# Ethernet.net
KiCad netlist of a schematic drawn in Altium Designer
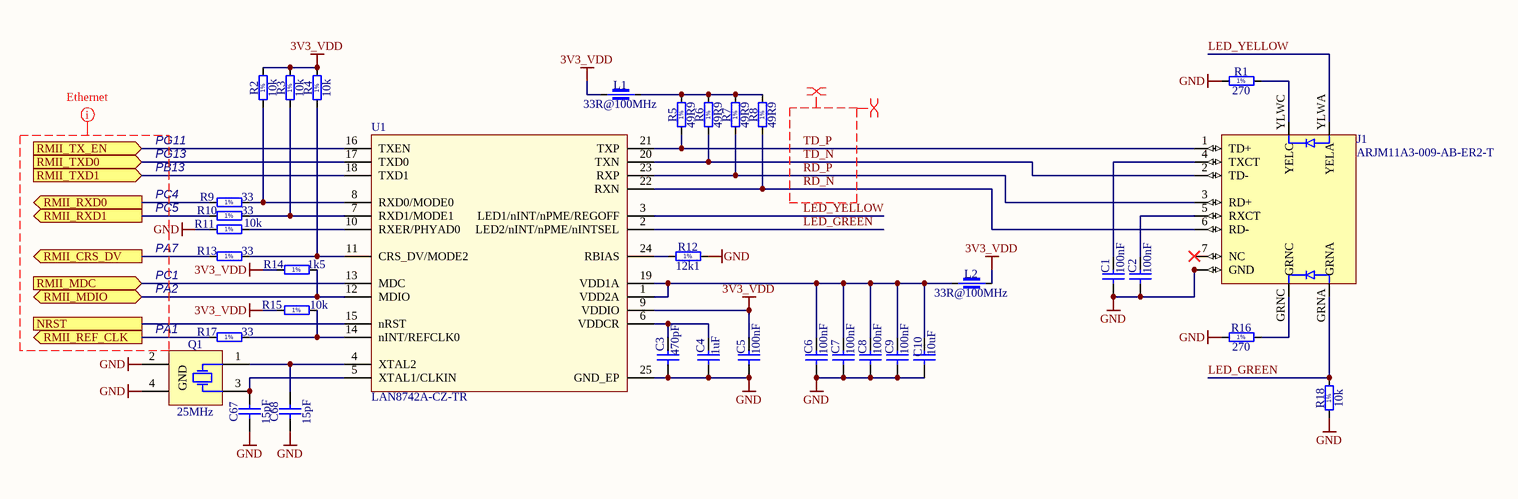
[diagram p0: Ethernet.SchDoc]

(export (version "E")
  (design (tool "Eeschema 10.0.6"))
  (components
    (comp (ref "C1")
      (value "100nF")
      (footprint "CAPC1005X55N")
      (description "Non-polarised capacitor")
      (fields
        (field (name "PART NUMBER") "CC0402_100NF_16V_10%_X7R")
        (field (name "VOLTAGE") "16V")
        (field (name "AUTHOR") "CERN DEM JLC")
      )
      (libsource (lib "Capacitors") (part "Capacitor - non polarized"))
    )
    (comp (ref "C2")
      (value "100nF")
      (footprint "CAPC1005X55N")
      (description "Non-polarised capacitor")
      (fields
        (field (name "PART NUMBER") "CC0402_100NF_16V_10%_X7R")
        (field (name "VOLTAGE") "16V")
        (field (name "AUTHOR") "CERN DEM JLC")
      )
      (libsource (lib "Capacitors") (part "Capacitor - non polarized"))
    )
    (comp (ref "C3")
      (value "470pF")
      (footprint "CAPC1005X55N")
      (description "Non-polarised capacitor")
      (fields
        (field (name "PART NUMBER") "CC0402_470PF_50V_10%_X7R")
        (field (name "VOLTAGE") "50V")
        (field (name "AUTHOR") "CERN DEM JLC")
      )
      (libsource (lib "Capacitors") (part "Capacitor - non polarized"))
    )
    (comp (ref "C4")
      (value "1uF")
      (footprint "CAPC1005X55N")
      (description "Non-polarised capacitor")
      (fields
        (field (name "PART NUMBER") "CC0402_1UF_16V_10%_X5R")
        (field (name "VOLTAGE") "16V")
        (field (name "AUTHOR") "CERN DEM JLC")
      )
      (libsource (lib "Capacitors") (part "Capacitor - non polarized"))
    )
    (comp (ref "C5")
      (value "100nF")
      (footprint "CAPC1005X55N")
      (description "Non-polarised capacitor")
      (fields
        (field (name "PART NUMBER") "CC0402_100NF_16V_10%_X7R")
        (field (name "VOLTAGE") "16V")
        (field (name "AUTHOR") "CERN DEM JLC")
      )
      (libsource (lib "Capacitors") (part "Capacitor - non polarized"))
    )
    (comp (ref "C6")
      (value "100nF")
      (footprint "CAPC1005X55N")
      (description "Non-polarised capacitor")
      (fields
        (field (name "PART NUMBER") "CC0402_100NF_16V_10%_X7R")
        (field (name "VOLTAGE") "16V")
        (field (name "AUTHOR") "CERN DEM JLC")
      )
      (libsource (lib "Capacitors") (part "Capacitor - non polarized"))
    )
    (comp (ref "C7")
      (value "100nF")
      (footprint "CAPC1005X55N")
      (description "Non-polarised capacitor")
      (fields
        (field (name "PART NUMBER") "CC0402_100NF_16V_10%_X7R")
        (field (name "VOLTAGE") "16V")
        (field (name "AUTHOR") "CERN DEM JLC")
      )
      (libsource (lib "Capacitors") (part "Capacitor - non polarized"))
    )
    (comp (ref "C8")
      (value "100nF")
      (footprint "CAPC1005X55N")
      (description "Non-polarised capacitor")
      (fields
        (field (name "PART NUMBER") "CC0402_100NF_16V_10%_X7R")
        (field (name "VOLTAGE") "16V")
        (field (name "AUTHOR") "CERN DEM JLC")
      )
      (libsource (lib "Capacitors") (part "Capacitor - non polarized"))
    )
    (comp (ref "C9")
      (value "100nF")
      (footprint "CAPC1005X55N")
      (description "Non-polarised capacitor")
      (fields
        (field (name "PART NUMBER") "CC0402_100NF_16V_10%_X7R")
        (field (name "VOLTAGE") "16V")
        (field (name "AUTHOR") "CERN DEM JLC")
      )
      (libsource (lib "Capacitors") (part "Capacitor - non polarized"))
    )
    (comp (ref "C10")
      (value "10uF")
      (footprint "CAPC1005X70N")
      (description "Non-polarised capacitor")
      (fields
        (field (name "PART NUMBER") "CC0402_10UF_6.3V_20%_X5R")
        (field (name "VOLTAGE") "6.3V")
        (field (name "AUTHOR") "CERN DEM JLC")
      )
      (libsource (lib "Capacitors") (part "Capacitor - non polarized"))
    )
    (comp (ref "C67")
      (value "15pF")
      (footprint "CAPC1005X55N")
      (description "Non-polarised capacitor")
      (fields
        (field (name "PART NUMBER") "CC0402_15PF_50V_5%_C0G")
        (field (name "VOLTAGE") "50V")
        (field (name "AUTHOR") "CERN DEM JLC")
      )
      (libsource (lib "Capacitors") (part "Capacitor - non polarized"))
    )
    (comp (ref "C68")
      (value "15pF")
      (footprint "CAPC1005X55N")
      (description "Non-polarised capacitor")
      (fields
        (field (name "PART NUMBER") "CC0402_15PF_50V_5%_C0G")
        (field (name "VOLTAGE") "50V")
        (field (name "AUTHOR") "CERN DEM JLC")
      )
      (libsource (lib "Capacitors") (part "Capacitor - non polarized"))
    )
    (comp (ref "J1")
      (value "ARJM11A3-009-AB-ER2-T")
      (footprint "ARJM11A3-009-AB-ER2-T")
      (description "1 Port RJ45 Magjack Connector Through Hole 10/100 Base-T, AutoMDIX")
      (fields (field (name "MF") "Abracon LLC"))
      (libsource (lib "MG_lib") (part "ARJM11A3-009-AB-ER2-T"))
    )
    (comp (ref "L1")
      (value "33R@100MHz")
      (footprint "INDC1005X55N")
      (fields
        (field (name "PART NUMBER") "IND0402_MURATA_BLM15PX330SN1D")
        (field (name "POWER") "3A")
        (field (name "TOLERANCE") "±25%")
        (field (name "AUTHOR") "CERN DEM JMW")
      )
      (libsource (lib "Inductors & Transformers") (part "Ferrite Bead"))
    )
    (comp (ref "L2")
      (value "33R@100MHz")
      (footprint "INDC1005X55N")
      (fields
        (field (name "PART NUMBER") "IND0402_MURATA_BLM15PX330SN1D")
        (field (name "POWER") "3A")
        (field (name "TOLERANCE") "±25%")
        (field (name "AUTHOR") "CERN DEM JMW")
      )
      (libsource (lib "Inductors & Transformers") (part "Ferrite Bead"))
    )
    (comp (ref "Q1")
      (value "25MHz")
      (footprint "XTAL_EPSON_TSX-3225")
      (description "Crystal 4 pins 1=XTAL Control 2=GND3=XTAL 4=GND")
      (fields
        (field (name "PART NUMBER") "XTAL_25MHZ_EPSON_TSX-3225 25.0000MF10Z-AC")
        (field (name "MANUFACTURER") "EPSON")
        (field (name "AUTHOR") "CERN DEM JLC")
      )
      (libsource (lib "ICs And Semiconductors") (part "Quartz Crystal 1X 2GND 3X 4GND"))
    )
    (comp (ref "R1")
      (value "270")
      (footprint "RESC1005X40N")
      (description "Resistor - 1%")
      (fields
        (field (name "PART NUMBER") "R0402_270R_1%_0.0625W_100PPM")
        (field (name "POWER") "0.0625W")
        (field (name "AUTHOR") "CERN DEM JLC")
      )
      (libsource (lib "Resistors") (part "Resistor - 1%"))
    )
    (comp (ref "R2")
      (value "10k")
      (footprint "RESC1005X40N")
      (description "Resistor - 1%")
      (fields
        (field (name "PART NUMBER") "R0402_10K_1%_0.0625W_100PPM")
        (field (name "POWER") "0.0625W")
        (field (name "AUTHOR") "CERN DEM JLC")
      )
      (libsource (lib "Resistors") (part "Resistor - 1%"))
    )
    (comp (ref "R3")
      (value "10k")
      (footprint "RESC1005X40N")
      (description "Resistor - 1%")
      (fields
        (field (name "PART NUMBER") "R0402_10K_1%_0.0625W_100PPM")
        (field (name "POWER") "0.0625W")
        (field (name "AUTHOR") "CERN DEM JLC")
      )
      (libsource (lib "Resistors") (part "Resistor - 1%"))
    )
    (comp (ref "R4")
      (value "10k")
      (footprint "RESC1005X40N")
      (description "Resistor - 1%")
      (fields
        (field (name "PART NUMBER") "R0402_10K_1%_0.0625W_100PPM")
        (field (name "POWER") "0.0625W")
        (field (name "AUTHOR") "CERN DEM JLC")
      )
      (libsource (lib "Resistors") (part "Resistor - 1%"))
    )
    (comp (ref "R5")
      (value "49R9")
      (footprint "RESC1005X40N")
      (description "Resistor - 1%")
      (fields
        (field (name "PART NUMBER") "R0402_49R9_1%_0.0625W_100PPM")
        (field (name "POWER") "0.0625W")
        (field (name "AUTHOR") "CERN DEM JLC")
      )
      (libsource (lib "Resistors") (part "Resistor - 1%"))
    )
    (comp (ref "R6")
      (value "49R9")
      (footprint "RESC1005X40N")
      (description "Resistor - 1%")
      (fields
        (field (name "PART NUMBER") "R0402_49R9_1%_0.0625W_100PPM")
        (field (name "POWER") "0.0625W")
        (field (name "AUTHOR") "CERN DEM JLC")
      )
      (libsource (lib "Resistors") (part "Resistor - 1%"))
    )
    (comp (ref "R7")
      (value "49R9")
      (footprint "RESC1005X40N")
      (description "Resistor - 1%")
      (fields
        (field (name "PART NUMBER") "R0402_49R9_1%_0.0625W_100PPM")
        (field (name "POWER") "0.0625W")
        (field (name "AUTHOR") "CERN DEM JLC")
      )
      (libsource (lib "Resistors") (part "Resistor - 1%"))
    )
    (comp (ref "R8")
      (value "49R9")
      (footprint "RESC1005X40N")
      (description "Resistor - 1%")
      (fields
        (field (name "PART NUMBER") "R0402_49R9_1%_0.0625W_100PPM")
        (field (name "POWER") "0.0625W")
        (field (name "AUTHOR") "CERN DEM JLC")
      )
      (libsource (lib "Resistors") (part "Resistor - 1%"))
    )
    (comp (ref "R9")
      (value "33")
      (footprint "RESC1005X40N")
      (description "Resistor - 1%")
      (fields
        (field (name "PART NUMBER") "R0402_33R_1%_0.0625W_100PPM")
        (field (name "POWER") "0.0625W")
        (field (name "AUTHOR") "CERN DEM JLC")
      )
      (libsource (lib "Resistors") (part "Resistor - 1%"))
    )
    (comp (ref "R10")
      (value "33")
      (footprint "RESC1005X40N")
      (description "Resistor - 1%")
      (fields
        (field (name "PART NUMBER") "R0402_33R_1%_0.0625W_100PPM")
        (field (name "POWER") "0.0625W")
        (field (name "AUTHOR") "CERN DEM JLC")
      )
      (libsource (lib "Resistors") (part "Resistor - 1%"))
    )
    (comp (ref "R11")
      (value "10k")
      (footprint "RESC1005X40N")
      (description "Resistor - 1%")
      (fields
        (field (name "PART NUMBER") "R0402_10K_1%_0.0625W_100PPM")
        (field (name "POWER") "0.0625W")
        (field (name "AUTHOR") "CERN DEM JLC")
      )
      (libsource (lib "Resistors") (part "Resistor - 1%"))
    )
    (comp (ref "R12")
      (value "12k1")
      (footprint "RESC1005X40N")
      (description "Resistor - 1%")
      (fields
        (field (name "PART NUMBER") "R0402_12K1_1%_0.0625W_100PPM")
        (field (name "POWER") "0.0625W")
        (field (name "AUTHOR") "CERN DEM JLC")
      )
      (libsource (lib "Resistors") (part "Resistor - 1%"))
    )
    (comp (ref "R13")
      (value "33")
      (footprint "RESC1005X40N")
      (description "Resistor - 1%")
      (fields
        (field (name "PART NUMBER") "R0402_33R_1%_0.0625W_100PPM")
        (field (name "POWER") "0.0625W")
        (field (name "AUTHOR") "CERN DEM JLC")
      )
      (libsource (lib "Resistors") (part "Resistor - 1%"))
    )
    (comp (ref "R14")
      (value "1k5")
      (footprint "RESC1005X40N")
      (description "Resistor - 1%")
      (fields
        (field (name "PART NUMBER") "R0402_1K5_1%_0.0625W_100PPM")
        (field (name "POWER") "0.0625W")
        (field (name "AUTHOR") "CERN DEM JLC")
      )
      (libsource (lib "Resistors") (part "Resistor - 1%"))
    )
    (comp (ref "R15")
      (value "10k")
      (footprint "RESC1005X40N")
      (description "Resistor - 1%")
      (fields
        (field (name "PART NUMBER") "R0402_10K_1%_0.0625W_100PPM")
        (field (name "POWER") "0.0625W")
        (field (name "AUTHOR") "CERN DEM JLC")
      )
      (libsource (lib "Resistors") (part "Resistor - 1%"))
    )
    (comp (ref "R16")
      (value "270")
      (footprint "RESC1005X40N")
      (description "Resistor - 1%")
      (fields
        (field (name "PART NUMBER") "R0402_270R_1%_0.0625W_100PPM")
        (field (name "POWER") "0.0625W")
        (field (name "AUTHOR") "CERN DEM JLC")
      )
      (libsource (lib "Resistors") (part "Resistor - 1%"))
    )
    (comp (ref "R17")
      (value "33")
      (footprint "RESC1005X40N")
      (description "Resistor - 1%")
      (fields
        (field (name "PART NUMBER") "R0402_33R_1%_0.0625W_100PPM")
        (field (name "POWER") "0.0625W")
        (field (name "AUTHOR") "CERN DEM JLC")
      )
      (libsource (lib "Resistors") (part "Resistor - 1%"))
    )
    (comp (ref "R18")
      (value "10k")
      (footprint "RESC1005X40N")
      (description "Resistor - 1%")
      (fields
        (field (name "PART NUMBER") "R0402_10K_1%_0.0625W_100PPM")
        (field (name "POWER") "0.0625W")
        (field (name "AUTHOR") "CERN DEM JLC")
      )
      (libsource (lib "Resistors") (part "Resistor - 1%"))
    )
    (comp (ref "U1")
      (value "LAN8742A-CZ-TR")
      (footprint "QFN24_0R5_4X4")
      (libsource (lib "MB1137") (part "LAN8742A-CZ-TR"))
    )
  )
  (nets
    (net (code "1") (name "/LED_GREEN") (class "Default")
      (node (ref "J1") (pin "GRNA") (pinfunction "GRNA_GRNA") (pintype "bidirectional"))
      (node (ref "R18") (pin "2") (pinfunction "2_2") (pintype "passive"))
      (node (ref "U1") (pin "2") (pinfunction "LED2/nINT/nPME/nINTSEL_2") (pintype "passive"))
    )
    (net (code "2") (name "/LED_YELLOW") (class "Default")
      (node (ref "J1") (pin "YLWA") (pinfunction "YELA_YLWA") (pintype "bidirectional"))
      (node (ref "U1") (pin "3") (pinfunction "LED1/nINT/nPME/REGOFF_3") (pintype "passive"))
    )
    (net (code "3") (name "/NRST") (class "Default")
      (node (ref "U1") (pin "15") (pinfunction "nRST_15") (pintype "passive"))
    )
    (net (code "4") (name "/RD_N") (class "Default")
      (node (ref "J1") (pin "6") (pinfunction "RD-_6") (pintype "bidirectional"))
      (node (ref "R8") (pin "1") (pinfunction "1_1") (pintype "passive"))
      (node (ref "U1") (pin "22") (pinfunction "RXN_22") (pintype "passive"))
    )
    (net (code "5") (name "/RD_P") (class "Default")
      (node (ref "J1") (pin "3") (pinfunction "RD+_3") (pintype "bidirectional"))
      (node (ref "R7") (pin "1") (pinfunction "1_1") (pintype "passive"))
      (node (ref "U1") (pin "23") (pinfunction "RXP_23") (pintype "passive"))
    )
    (net (code "6") (name "/RMII_CRS_DV") (class "Default")
      (node (ref "R13") (pin "1") (pinfunction "1_1") (pintype "passive"))
    )
    (net (code "7") (name "/RMII_MDC") (class "Default")
      (node (ref "U1") (pin "13") (pinfunction "MDC_13") (pintype "passive"))
    )
    (net (code "8") (name "/RMII_MDIO") (class "Default")
      (node (ref "R14") (pin "2") (pinfunction "2_2") (pintype "passive"))
      (node (ref "U1") (pin "12") (pinfunction "MDIO_12") (pintype "passive"))
    )
    (net (code "9") (name "/RMII_REF_CLK") (class "Default")
      (node (ref "R17") (pin "1") (pinfunction "1_1") (pintype "passive"))
    )
    (net (code "10") (name "/RMII_RXD0") (class "Default")
      (node (ref "R9") (pin "1") (pinfunction "1_1") (pintype "passive"))
    )
    (net (code "11") (name "/RMII_RXD1") (class "Default")
      (node (ref "R10") (pin "1") (pinfunction "1_1") (pintype "passive"))
    )
    (net (code "12") (name "/RMII_TXD0") (class "Default")
      (node (ref "U1") (pin "17") (pinfunction "TXD0_17") (pintype "passive"))
    )
    (net (code "13") (name "/RMII_TXD1") (class "Default")
      (node (ref "U1") (pin "18") (pinfunction "TXD1_18") (pintype "passive"))
    )
    (net (code "14") (name "/RMII_TX_EN") (class "Default")
      (node (ref "U1") (pin "16") (pinfunction "TXEN_16") (pintype "passive"))
    )
    (net (code "15") (name "/TD_N") (class "Default")
      (node (ref "J1") (pin "2") (pinfunction "TD-_2") (pintype "bidirectional"))
      (node (ref "R6") (pin "1") (pinfunction "1_1") (pintype "passive"))
      (node (ref "U1") (pin "20") (pinfunction "TXN_20") (pintype "passive"))
    )
    (net (code "16") (name "/TD_P") (class "Default")
      (node (ref "J1") (pin "1") (pinfunction "TD+_1") (pintype "bidirectional"))
      (node (ref "R5") (pin "1") (pinfunction "1_1") (pintype "passive"))
      (node (ref "U1") (pin "21") (pinfunction "TXP_21") (pintype "passive"))
    )
    (net (code "17") (name "3V3_VDD") (class "Default")
      (node (ref "C5") (pin "2") (pinfunction "2_2") (pintype "passive"))
      (node (ref "L1") (pin "1") (pinfunction "1_1") (pintype "passive"))
      (node (ref "L2") (pin "2") (pinfunction "2_2") (pintype "passive"))
      (node (ref "R14") (pin "1") (pinfunction "1_1") (pintype "passive"))
      (node (ref "R15") (pin "1") (pinfunction "1_1") (pintype "passive"))
      (node (ref "R2") (pin "2") (pinfunction "2_2") (pintype "passive"))
      (node (ref "R3") (pin "2") (pinfunction "2_2") (pintype "passive"))
      (node (ref "R4") (pin "2") (pinfunction "2_2") (pintype "passive"))
      (node (ref "U1") (pin "9") (pinfunction "VDDIO_9") (pintype "passive"))
    )
    (net (code "18") (name "GND") (class "Default")
      (node (ref "C1") (pin "1") (pinfunction "1_1") (pintype "passive"))
      (node (ref "C10") (pin "1") (pinfunction "1_1") (pintype "passive"))
      (node (ref "C2") (pin "1") (pinfunction "1_1") (pintype "passive"))
      (node (ref "C3") (pin "1") (pinfunction "1_1") (pintype "passive"))
      (node (ref "C4") (pin "1") (pinfunction "1_1") (pintype "passive"))
      (node (ref "C5") (pin "1") (pinfunction "1_1") (pintype "passive"))
      (node (ref "C6") (pin "1") (pinfunction "1_1") (pintype "passive"))
      (node (ref "C67") (pin "1") (pinfunction "1_1") (pintype "passive"))
      (node (ref "C68") (pin "1") (pinfunction "1_1") (pintype "passive"))
      (node (ref "C7") (pin "1") (pinfunction "1_1") (pintype "passive"))
      (node (ref "C8") (pin "1") (pinfunction "1_1") (pintype "passive"))
      (node (ref "C9") (pin "1") (pinfunction "1_1") (pintype "passive"))
      (node (ref "J1") (pin "8") (pinfunction "GND_8") (pintype "bidirectional"))
      (node (ref "J1") (pin "P$3") (pinfunction "GND_P$3") (pintype "bidirectional"))
      (node (ref "J1") (pin "P$4") (pinfunction "GND_P$4") (pintype "bidirectional"))
      (node (ref "Q1") (pin "2") (pinfunction "GND_2") (pintype "power_in"))
      (node (ref "Q1") (pin "4") (pinfunction "GND_4") (pintype "power_in"))
      (node (ref "R1") (pin "1") (pinfunction "1_1") (pintype "passive"))
      (node (ref "R11") (pin "1") (pinfunction "1_1") (pintype "passive"))
      (node (ref "R12") (pin "2") (pinfunction "2_2") (pintype "passive"))
      (node (ref "R16") (pin "1") (pinfunction "1_1") (pintype "passive"))
      (node (ref "R18") (pin "1") (pinfunction "1_1") (pintype "passive"))
      (node (ref "U1") (pin "25") (pinfunction "GND_EP_25") (pintype "passive"))
    )
    (net (code "19") (name "Net-(J1-PadGRNC)") (class "Default")
      (node (ref "J1") (pin "GRNC") (pinfunction "GRNC_GRNC") (pintype "bidirectional"))
      (node (ref "R16") (pin "2") (pinfunction "2_2") (pintype "passive"))
    )
    (net (code "20") (name "Net-(J1-RXCT)") (class "Default")
      (node (ref "C2") (pin "2") (pinfunction "2_2") (pintype "passive"))
      (node (ref "J1") (pin "5") (pinfunction "RXCT_5") (pintype "bidirectional"))
    )
    (net (code "21") (name "Net-(J1-TXCT)") (class "Default")
      (node (ref "C1") (pin "2") (pinfunction "2_2") (pintype "passive"))
      (node (ref "J1") (pin "4") (pinfunction "TXCT_4") (pintype "bidirectional"))
    )
    (net (code "22") (name "Net-(J1-YELC)") (class "Default")
      (node (ref "J1") (pin "YLWC") (pinfunction "YELC_YLWC") (pintype "bidirectional"))
      (node (ref "R1") (pin "2") (pinfunction "2_2") (pintype "passive"))
    )
    (net (code "23") (name "Net-(L1-Pad2)") (class "Default")
      (node (ref "L1") (pin "2") (pinfunction "2_2") (pintype "passive"))
      (node (ref "R5") (pin "2") (pinfunction "2_2") (pintype "passive"))
      (node (ref "R6") (pin "2") (pinfunction "2_2") (pintype "passive"))
      (node (ref "R7") (pin "2") (pinfunction "2_2") (pintype "passive"))
      (node (ref "R8") (pin "2") (pinfunction "2_2") (pintype "passive"))
    )
    (net (code "24") (name "Net-(U1-CRS_DV{slash}MODE2)") (class "Default")
      (node (ref "R13") (pin "2") (pinfunction "2_2") (pintype "passive"))
      (node (ref "R4") (pin "1") (pinfunction "1_1") (pintype "passive"))
      (node (ref "U1") (pin "11") (pinfunction "CRS_DV/MODE2_11") (pintype "passive"))
    )
    (net (code "25") (name "Net-(U1-RBIAS)") (class "Default")
      (node (ref "R12") (pin "1") (pinfunction "1_1") (pintype "passive"))
      (node (ref "U1") (pin "24") (pinfunction "RBIAS_24") (pintype "passive"))
    )
    (net (code "26") (name "Net-(U1-RXD0{slash}MODE0)") (class "Default")
      (node (ref "R2") (pin "1") (pinfunction "1_1") (pintype "passive"))
      (node (ref "R9") (pin "2") (pinfunction "2_2") (pintype "passive"))
      (node (ref "U1") (pin "8") (pinfunction "RXD0/MODE0_8") (pintype "passive"))
    )
    (net (code "27") (name "Net-(U1-RXD1{slash}MODE1)") (class "Default")
      (node (ref "R10") (pin "2") (pinfunction "2_2") (pintype "passive"))
      (node (ref "R3") (pin "1") (pinfunction "1_1") (pintype "passive"))
      (node (ref "U1") (pin "7") (pinfunction "RXD1/MODE1_7") (pintype "passive"))
    )
    (net (code "28") (name "Net-(U1-RXER{slash}PHYAD0)") (class "Default")
      (node (ref "R11") (pin "2") (pinfunction "2_2") (pintype "passive"))
      (node (ref "U1") (pin "10") (pinfunction "RXER/PHYAD0_10") (pintype "passive"))
    )
    (net (code "29") (name "Net-(U1-VDD1A)") (class "Default")
      (node (ref "C10") (pin "2") (pinfunction "2_2") (pintype "passive"))
      (node (ref "C6") (pin "2") (pinfunction "2_2") (pintype "passive"))
      (node (ref "C7") (pin "2") (pinfunction "2_2") (pintype "passive"))
      (node (ref "C8") (pin "2") (pinfunction "2_2") (pintype "passive"))
      (node (ref "C9") (pin "2") (pinfunction "2_2") (pintype "passive"))
      (node (ref "L2") (pin "1") (pinfunction "1_1") (pintype "passive"))
      (node (ref "U1") (pin "1") (pinfunction "VDD2A_1") (pintype "passive"))
      (node (ref "U1") (pin "19") (pinfunction "VDD1A_19") (pintype "passive"))
    )
    (net (code "30") (name "Net-(U1-VDDCR)") (class "Default")
      (node (ref "C3") (pin "2") (pinfunction "2_2") (pintype "passive"))
      (node (ref "C4") (pin "2") (pinfunction "2_2") (pintype "passive"))
      (node (ref "U1") (pin "6") (pinfunction "VDDCR_6") (pintype "passive"))
    )
    (net (code "31") (name "Net-(U1-XTAL1{slash}CLKIN)") (class "Default")
      (node (ref "C67") (pin "2") (pinfunction "2_2") (pintype "passive"))
      (node (ref "Q1") (pin "3") (pinfunction "X_3") (pintype "passive"))
      (node (ref "U1") (pin "5") (pinfunction "XTAL1/CLKIN_5") (pintype "passive"))
    )
    (net (code "32") (name "Net-(U1-XTAL2)") (class "Default")
      (node (ref "C68") (pin "2") (pinfunction "2_2") (pintype "passive"))
      (node (ref "Q1") (pin "1") (pinfunction "X_1") (pintype "passive"))
      (node (ref "U1") (pin "4") (pinfunction "XTAL2_4") (pintype "passive"))
    )
    (net (code "33") (name "Net-(U1-nINT{slash}REFCLK0)") (class "Default")
      (node (ref "R15") (pin "2") (pinfunction "2_2") (pintype "passive"))
      (node (ref "R17") (pin "2") (pinfunction "2_2") (pintype "passive"))
      (node (ref "U1") (pin "14") (pinfunction "nINT/REFCLK0_14") (pintype "passive"))
    )
    (net (code "34") (name "unconnected-(J1-NC-Pad7)") (class "Default")
      (node (ref "J1") (pin "7") (pinfunction "NC_7") (pintype "bidirectional+no_connect"))
    )
  )
)
